# MCU023_MSP432E_Ethernet_Power.net
KiCad netlist of a schematic drawn in Altium Designer
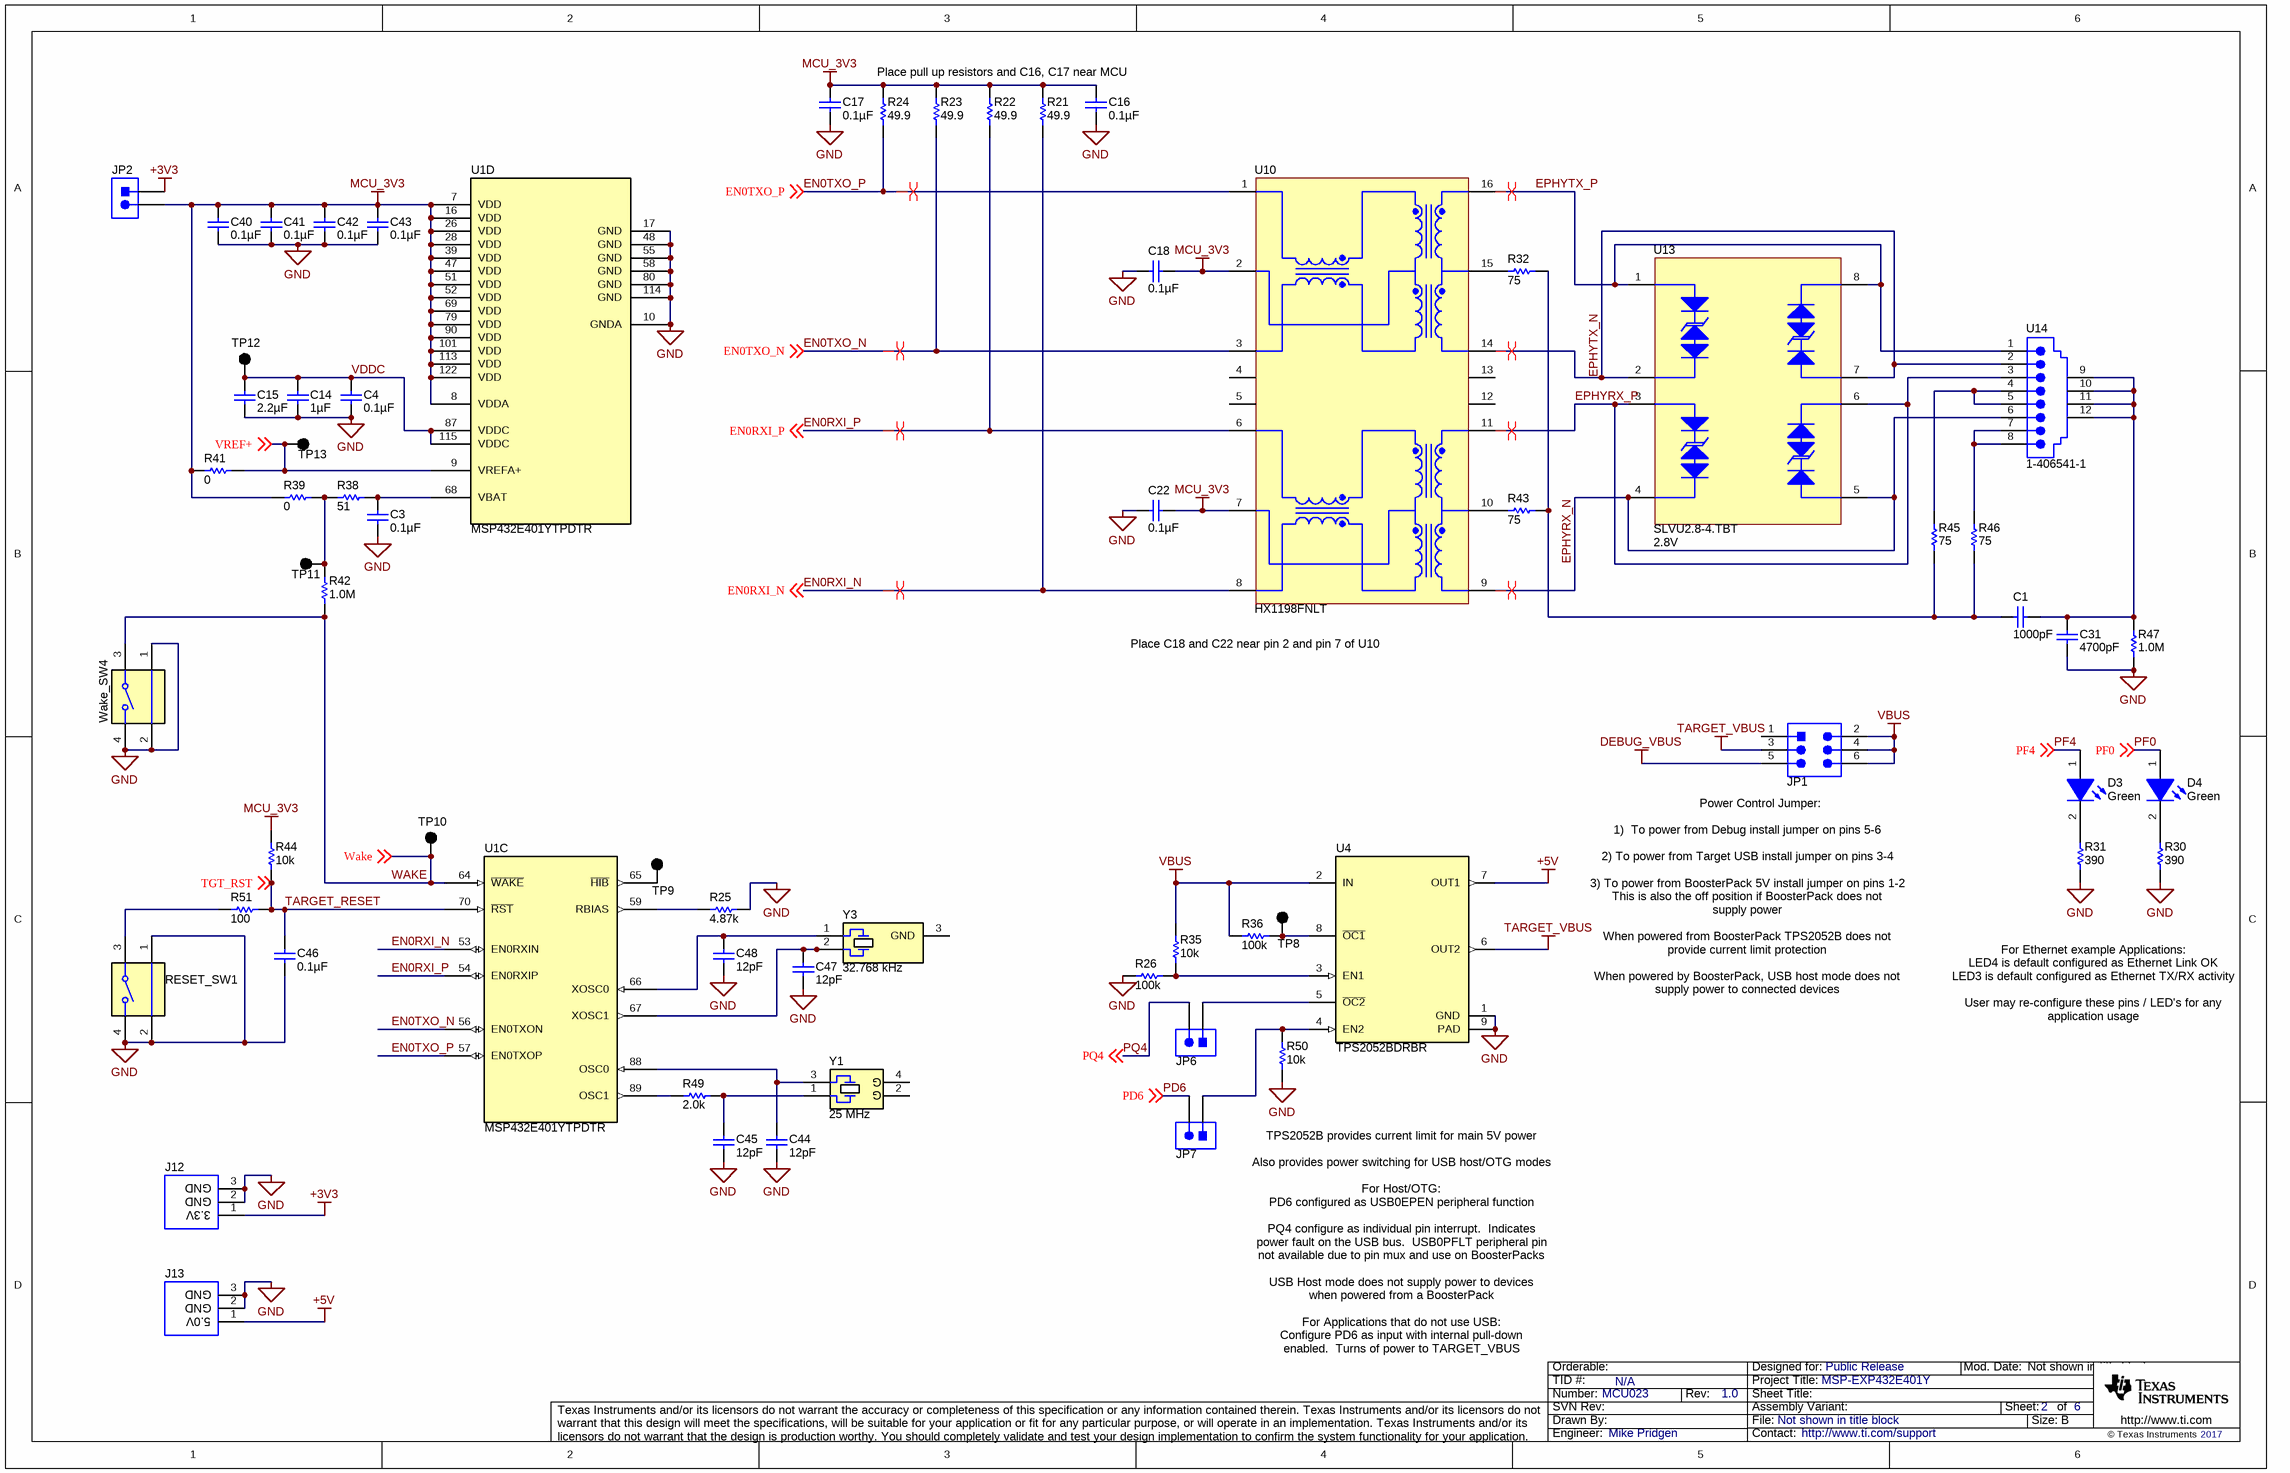
[diagram p0: MCU023_MSP432E_Ethernet_Power.SchDoc]

(export (version "E")
  (design (tool "Eeschema 10.0.6"))
  (components
    (comp (ref "C1")
      (value "C1210C102KGRACTU")
      (footprint "1210_270")
      (description "CAP, CERM, 1000 pF, 2000 V, +/- 10%, X7R, 1210")
      (fields
        (field (name "VALUEDISPLAYED") "1000pF")
        (field (name "MANUFACTURER") "Kemet")
        (field (name "PUBLISHER") "Texas Instruments")
      )
      (libsource (lib "Capacitor_Ceramic") (part "C1210C102KGRACTU"))
    )
    (comp (ref "C3")
      (value "GRM155R71C104KA88D")
      (footprint "0402")
      (description "CAP, CERM, 0.1 µF, 16 V, +/- 10%, X7R, 0402")
      (fields
        (field (name "VALUEDISPLAYED") "0.1µF")
        (field (name "MANUFACTURER") "MuRata")
        (field (name "PUBLISHER") "Texas Instruments")
      )
      (libsource (lib "Capacitor_Ceramic") (part "GRM155R71C104KA88D"))
    )
    (comp (ref "C4")
      (value "GRM155R71C104KA88D")
      (footprint "0402")
      (description "CAP, CERM, 0.1 µF, 16 V, +/- 10%, X7R, 0402")
      (fields
        (field (name "VALUEDISPLAYED") "0.1µF")
        (field (name "MANUFACTURER") "MuRata")
        (field (name "PUBLISHER") "Texas Instruments")
      )
      (libsource (lib "Capacitor_Ceramic") (part "GRM155R71C104KA88D"))
    )
    (comp (ref "C14")
      (value "GRM155R61A105KE15D")
      (footprint "0402")
      (description "CAP, CERM, 1 µF, 10 V, +/- 10%, X5R, 0402")
      (fields
        (field (name "VALUEDISPLAYED") "1µF")
        (field (name "MANUFACTURER") "MuRata")
        (field (name "PUBLISHER") "Texas Instruments")
      )
      (libsource (lib "Capacitor_Ceramic") (part "GRM155R61A105KE15D"))
    )
    (comp (ref "C15")
      (value "GRM188R61C225KE15D")
      (footprint "0603")
      (description "CAP, CERM, 2.2 µF, 16 V, +/- 10%, X5R, 0603")
      (fields
        (field (name "VALUEDISPLAYED") "2.2µF")
        (field (name "MANUFACTURER") "MuRata")
        (field (name "PUBLISHER") "Texas Instruments")
      )
      (libsource (lib "Capacitor_Ceramic") (part "GRM188R61C225KE15D"))
    )
    (comp (ref "C16")
      (value "GRM155R71C104KA88D")
      (footprint "0402")
      (description "CAP, CERM, 0.1 µF, 16 V, +/- 10%, X7R, 0402")
      (fields
        (field (name "VALUEDISPLAYED") "0.1µF")
        (field (name "MANUFACTURER") "MuRata")
        (field (name "PUBLISHER") "Texas Instruments")
      )
      (libsource (lib "Capacitor_Ceramic") (part "GRM155R71C104KA88D"))
    )
    (comp (ref "C17")
      (value "GRM155R71C104KA88D")
      (footprint "0402")
      (description "CAP, CERM, 0.1 µF, 16 V, +/- 10%, X7R, 0402")
      (fields
        (field (name "VALUEDISPLAYED") "0.1µF")
        (field (name "MANUFACTURER") "MuRata")
        (field (name "PUBLISHER") "Texas Instruments")
      )
      (libsource (lib "Capacitor_Ceramic") (part "GRM155R71C104KA88D"))
    )
    (comp (ref "C18")
      (value "GRM155R71C104KA88D")
      (footprint "0402")
      (description "CAP, CERM, 0.1 µF, 16 V, +/- 10%, X7R, 0402")
      (fields
        (field (name "VALUEDISPLAYED") "0.1µF")
        (field (name "MANUFACTURER") "MuRata")
        (field (name "PUBLISHER") "Texas Instruments")
      )
      (libsource (lib "Capacitor_Ceramic") (part "GRM155R71C104KA88D"))
    )
    (comp (ref "C22")
      (value "GRM155R71C104KA88D")
      (footprint "0402")
      (description "CAP, CERM, 0.1 µF, 16 V, +/- 10%, X7R, 0402")
      (fields
        (field (name "VALUEDISPLAYED") "0.1µF")
        (field (name "MANUFACTURER") "MuRata")
        (field (name "PUBLISHER") "Texas Instruments")
      )
      (libsource (lib "Capacitor_Ceramic") (part "GRM155R71C104KA88D"))
    )
    (comp (ref "C31")
      (value "1812GC472KAT1A")
      (footprint "1812_254")
      (description "CAP, CERM, 4700 pF, 2000 V, +/- 10%, X7R, 1812")
      (fields
        (field (name "VALUEDISPLAYED") "4700pF")
        (field (name "MANUFACTURER") "AVX")
        (field (name "PUBLISHER") "Texas Instruments")
      )
      (libsource (lib "Capacitor_Ceramic") (part "1812GC472KAT1A"))
    )
    (comp (ref "C40")
      (value "GRM155R71C104KA88D")
      (footprint "0402")
      (description "CAP, CERM, 0.1 µF, 16 V, +/- 10%, X7R, 0402")
      (fields
        (field (name "VALUEDISPLAYED") "0.1µF")
        (field (name "MANUFACTURER") "MuRata")
        (field (name "PUBLISHER") "Texas Instruments")
      )
      (libsource (lib "Capacitor_Ceramic") (part "GRM155R71C104KA88D"))
    )
    (comp (ref "C41")
      (value "GRM155R71C104KA88D")
      (footprint "0402")
      (description "CAP, CERM, 0.1 µF, 16 V, +/- 10%, X7R, 0402")
      (fields
        (field (name "VALUEDISPLAYED") "0.1µF")
        (field (name "MANUFACTURER") "MuRata")
        (field (name "PUBLISHER") "Texas Instruments")
      )
      (libsource (lib "Capacitor_Ceramic") (part "GRM155R71C104KA88D"))
    )
    (comp (ref "C42")
      (value "GRM155R71C104KA88D")
      (footprint "0402")
      (description "CAP, CERM, 0.1 µF, 16 V, +/- 10%, X7R, 0402")
      (fields
        (field (name "VALUEDISPLAYED") "0.1µF")
        (field (name "MANUFACTURER") "MuRata")
        (field (name "PUBLISHER") "Texas Instruments")
      )
      (libsource (lib "Capacitor_Ceramic") (part "GRM155R71C104KA88D"))
    )
    (comp (ref "C43")
      (value "GRM155R71C104KA88D")
      (footprint "0402")
      (description "CAP, CERM, 0.1 µF, 16 V, +/- 10%, X7R, 0402")
      (fields
        (field (name "VALUEDISPLAYED") "0.1µF")
        (field (name "MANUFACTURER") "MuRata")
        (field (name "PUBLISHER") "Texas Instruments")
      )
      (libsource (lib "Capacitor_Ceramic") (part "GRM155R71C104KA88D"))
    )
    (comp (ref "C44")
      (value "GRM1555C1H120JA01D")
      (footprint "0402")
      (description "CAP, CERM, 12 pF, 50 V, +/- 5%, C0G/NP0, 0402")
      (fields
        (field (name "VALUEDISPLAYED") "12pF")
        (field (name "MANUFACTURER") "MuRata")
        (field (name "PUBLISHER") "Texas Instruments")
      )
      (libsource (lib "Capacitor_Ceramic") (part "GRM1555C1H120JA01D"))
    )
    (comp (ref "C45")
      (value "GRM1555C1H120JA01D")
      (footprint "0402")
      (description "CAP, CERM, 12 pF, 50 V, +/- 5%, C0G/NP0, 0402")
      (fields
        (field (name "VALUEDISPLAYED") "12pF")
        (field (name "MANUFACTURER") "MuRata")
        (field (name "PUBLISHER") "Texas Instruments")
      )
      (libsource (lib "Capacitor_Ceramic") (part "GRM1555C1H120JA01D"))
    )
    (comp (ref "C46")
      (value "GRM155R71C104KA88D")
      (footprint "0402")
      (description "CAP, CERM, 0.1 µF, 16 V, +/- 10%, X7R, 0402")
      (fields
        (field (name "VALUEDISPLAYED") "0.1µF")
        (field (name "MANUFACTURER") "MuRata")
        (field (name "PUBLISHER") "Texas Instruments")
      )
      (libsource (lib "Capacitor_Ceramic") (part "GRM155R71C104KA88D"))
    )
    (comp (ref "C47")
      (value "GRM1555C1H120JA01D")
      (footprint "0402")
      (description "CAP, CERM, 12 pF, 50 V, +/- 5%, C0G/NP0, 0402")
      (fields
        (field (name "VALUEDISPLAYED") "12pF")
        (field (name "MANUFACTURER") "MuRata")
        (field (name "PUBLISHER") "Texas Instruments")
      )
      (libsource (lib "Capacitor_Ceramic") (part "GRM1555C1H120JA01D"))
    )
    (comp (ref "C48")
      (value "GRM1555C1H120JA01D")
      (footprint "0402")
      (description "CAP, CERM, 12 pF, 50 V, +/- 5%, C0G/NP0, 0402")
      (fields
        (field (name "VALUEDISPLAYED") "12pF")
        (field (name "MANUFACTURER") "MuRata")
        (field (name "PUBLISHER") "Texas Instruments")
      )
      (libsource (lib "Capacitor_Ceramic") (part "GRM1555C1H120JA01D"))
    )
    (comp (ref "D3")
      (value "Green")
      (footprint "LED_LTST-C190")
      (description "LED, Green, SMD")
      (fields
        (field (name "PARTNUMBER") "LTST-C190GKT")
        (field (name "MANUFACTURER") "Lite-On")
        (field (name "PUBLISHER") "Texas Instruments")
      )
      (libsource (lib "LED") (part "LTST-C190GKT"))
    )
    (comp (ref "D4")
      (value "Green")
      (footprint "LED_LTST-C190")
      (description "LED, Green, SMD")
      (fields
        (field (name "PARTNUMBER") "LTST-C190GKT")
        (field (name "MANUFACTURER") "Lite-On")
        (field (name "PUBLISHER") "Texas Instruments")
      )
      (libsource (lib "LED") (part "LTST-C190GKT"))
    )
    (comp (ref "J12")
      (value "PEC03SAAN")
      (footprint "PEC03SAAN_Launchpad_3V3")
      (description "Header, 100mil, 3x1, Tin, TH")
      (fields
        (field (name "MANUFACTURER") "Sullins Connector Solutions")
        (field (name "SYMBOLCREATOR") "a0412235")
        (field (name "PUBLISHER") "Texas Instruments")
      )
      (libsource (lib "") (part "PEC03SAAN_1"))
    )
    (comp (ref "J13")
      (value "PEC03SAAN")
      (footprint "PEC03SAAN_Launchpad_5V0")
      (description "Header, 100mil, 3x1, Tin, TH")
      (fields
        (field (name "MANUFACTURER") "Sullins Connector Solutions")
        (field (name "SYMBOLCREATOR") "a0412235")
        (field (name "PUBLISHER") "Texas Instruments")
      )
      (libsource (lib "Connectors_Sullins") (part "PEC03SAAN"))
    )
    (comp (ref "JP1")
      (value "PEC03DAAN")
      (footprint "SULLINS_PEC03DAAN")
      (description "Header, 100mil, 3x2, Tin, TH")
      (fields
        (field (name "MANUFACTURER") "Sullins Connector Solutions")
        (field (name "SYMBOLCREATOR") "a0412235")
        (field (name "PUBLISHER") "Texas Instruments")
      )
      (libsource (lib "Connectors_Sullins") (part "PEC03DAAN"))
    )
    (comp (ref "JP2")
      (value "PEC02SAAN")
      (footprint "CONN_PEC02SAAN")
      (description "Header, 100mil, 2x1, Tin, TH")
      (fields
        (field (name "MANUFACTURER") "Sullins Connector Solutions")
        (field (name "SYMBOLCREATOR") "a0412235")
        (field (name "PUBLISHER") "Texas Instruments")
      )
      (libsource (lib "Connectors_Sullins") (part "PEC02SAAN"))
    )
    (comp (ref "JP6")
      (value "PEC02SAAN")
      (footprint "CONN_PEC02SAAN")
      (description "Header, 100mil, 2x1, Tin, TH")
      (fields
        (field (name "MANUFACTURER") "Sullins Connector Solutions")
        (field (name "SYMBOLCREATOR") "a0412235")
        (field (name "PUBLISHER") "Texas Instruments")
      )
      (libsource (lib "Connectors_Sullins") (part "PEC02SAAN"))
    )
    (comp (ref "JP7")
      (value "PEC02SAAN")
      (footprint "CONN_PEC02SAAN")
      (description "Header, 100mil, 2x1, Tin, TH")
      (fields
        (field (name "MANUFACTURER") "Sullins Connector Solutions")
        (field (name "SYMBOLCREATOR") "a0412235")
        (field (name "PUBLISHER") "Texas Instruments")
      )
      (libsource (lib "Connectors_Sullins") (part "PEC02SAAN"))
    )
    (comp (ref "R21")
      (value "CRCW040249R9FKED")
      (footprint "0402")
      (description "RES, 49.9, 1%, 0.063 W, 0402")
      (fields
        (field (name "VALUEDISPLAYED") "49.9")
        (field (name "MANUFACTURER") "Vishay-Dale")
        (field (name "PUBLISHER") "Texas Instruments")
      )
      (libsource (lib "Resistor_0402") (part "CRCW040249R9FKED"))
    )
    (comp (ref "R22")
      (value "CRCW040249R9FKED")
      (footprint "0402")
      (description "RES, 49.9, 1%, 0.063 W, 0402")
      (fields
        (field (name "VALUEDISPLAYED") "49.9")
        (field (name "MANUFACTURER") "Vishay-Dale")
        (field (name "PUBLISHER") "Texas Instruments")
      )
      (libsource (lib "Resistor_0402") (part "CRCW040249R9FKED"))
    )
    (comp (ref "R23")
      (value "CRCW040249R9FKED")
      (footprint "0402")
      (description "RES, 49.9, 1%, 0.063 W, 0402")
      (fields
        (field (name "VALUEDISPLAYED") "49.9")
        (field (name "MANUFACTURER") "Vishay-Dale")
        (field (name "PUBLISHER") "Texas Instruments")
      )
      (libsource (lib "Resistor_0402") (part "CRCW040249R9FKED"))
    )
    (comp (ref "R24")
      (value "CRCW040249R9FKED")
      (footprint "0402")
      (description "RES, 49.9, 1%, 0.063 W, 0402")
      (fields
        (field (name "VALUEDISPLAYED") "49.9")
        (field (name "MANUFACTURER") "Vishay-Dale")
        (field (name "PUBLISHER") "Texas Instruments")
      )
      (libsource (lib "Resistor_0402") (part "CRCW040249R9FKED"))
    )
    (comp (ref "R25")
      (value "CRCW04024K87FKED")
      (footprint "0402")
      (description "RES, 4.87 k, 1%, 0.063 W, 0402")
      (fields
        (field (name "VALUEDISPLAYED") "4.87k")
        (field (name "MANUFACTURER") "Vishay-Dale")
        (field (name "PUBLISHER") "Texas Instruments")
      )
      (libsource (lib "Resistor_0402") (part "CRCW04024K87FKED"))
    )
    (comp (ref "R26")
      (value "CRCW0402100KJNED")
      (footprint "0402")
      (description "RES, 100 k, 5%, 0.063 W, 0402")
      (fields
        (field (name "VALUEDISPLAYED") "100k")
        (field (name "MANUFACTURER") "Vishay-Dale")
        (field (name "PUBLISHER") "Texas Instruments")
      )
      (libsource (lib "Resistor_0402") (part "CRCW0402100KJNED"))
    )
    (comp (ref "R30")
      (value "CRCW0402390RJNED")
      (footprint "0402")
      (description "RES, 390, 5%, 0.063 W, 0402")
      (fields
        (field (name "VALUEDISPLAYED") "390")
        (field (name "MANUFACTURER") "Vishay-Dale")
        (field (name "PUBLISHER") "Texas Instruments")
      )
      (libsource (lib "Resistor_0402") (part "CRCW0402390RJNED"))
    )
    (comp (ref "R31")
      (value "CRCW0402390RJNED")
      (footprint "0402")
      (description "RES, 390, 5%, 0.063 W, 0402")
      (fields
        (field (name "VALUEDISPLAYED") "390")
        (field (name "MANUFACTURER") "Vishay-Dale")
        (field (name "PUBLISHER") "Texas Instruments")
      )
      (libsource (lib "Resistor_0402") (part "CRCW0402390RJNED"))
    )
    (comp (ref "R32")
      (value "CRCW040275R0JNED")
      (footprint "0402")
      (description "RES, 75, 5%, 0.063 W, 0402")
      (fields
        (field (name "VALUEDISPLAYED") "75")
        (field (name "MANUFACTURER") "Vishay-Dale")
        (field (name "PUBLISHER") "Texas Instruments")
      )
      (libsource (lib "Resistor_0402") (part "CRCW040275R0JNED"))
    )
    (comp (ref "R35")
      (value "CRCW040210K0JNED")
      (footprint "0402")
      (description "RES, 10 k, 5%, 0.063 W, 0402")
      (fields
        (field (name "VALUEDISPLAYED") "10k")
        (field (name "MANUFACTURER") "Vishay-Dale")
        (field (name "PUBLISHER") "Texas Instruments")
      )
      (libsource (lib "Resistor_0402") (part "CRCW040210K0JNED"))
    )
    (comp (ref "R36")
      (value "CRCW0402100KJNED")
      (footprint "0402")
      (description "RES, 100 k, 5%, 0.063 W, 0402")
      (fields
        (field (name "VALUEDISPLAYED") "100k")
        (field (name "MANUFACTURER") "Vishay-Dale")
        (field (name "PUBLISHER") "Texas Instruments")
      )
      (libsource (lib "Resistor_0402") (part "CRCW0402100KJNED"))
    )
    (comp (ref "R38")
      (value "CRCW040251R0JNED")
      (footprint "0402")
      (description "RES, 51, 5%, 0.063 W, 0402")
      (fields
        (field (name "VALUEDISPLAYED") "51")
        (field (name "MANUFACTURER") "Vishay-Dale")
        (field (name "PUBLISHER") "Texas Instruments")
      )
      (libsource (lib "Resistor_0402") (part "CRCW040251R0JNED"))
    )
    (comp (ref "R39")
      (value "ERJ-2GE0R00X")
      (footprint "0402")
      (description "RES, 0, 5%, 0.063 W, 0402")
      (fields
        (field (name "VALUEDISPLAYED") "0")
        (field (name "MANUFACTURER") "Panasonic")
        (field (name "PUBLISHER") "Texas Instruments")
      )
      (libsource (lib "Resistor_0402") (part "ERJ-2GE0R00X"))
    )
    (comp (ref "R41")
      (value "ERJ-2GE0R00X")
      (footprint "0402")
      (description "RES, 0, 5%, 0.063 W, 0402")
      (fields
        (field (name "VALUEDISPLAYED") "0")
        (field (name "MANUFACTURER") "Panasonic")
        (field (name "PUBLISHER") "Texas Instruments")
      )
      (libsource (lib "Resistor_0402") (part "ERJ-2GE0R00X"))
    )
    (comp (ref "R42")
      (value "CRCW04021M00JNED")
      (footprint "0402")
      (description "RES, 1.0 M, 5%, 0.063 W, 0402")
      (fields
        (field (name "VALUEDISPLAYED") "1.0M")
        (field (name "MANUFACTURER") "Vishay-Dale")
        (field (name "PUBLISHER") "Texas Instruments")
      )
      (libsource (lib "Resistor_0402") (part "CRCW04021M00JNED"))
    )
    (comp (ref "R43")
      (value "CRCW040275R0JNED")
      (footprint "0402")
      (description "RES, 75, 5%, 0.063 W, 0402")
      (fields
        (field (name "VALUEDISPLAYED") "75")
        (field (name "MANUFACTURER") "Vishay-Dale")
        (field (name "PUBLISHER") "Texas Instruments")
      )
      (libsource (lib "Resistor_0402") (part "CRCW040275R0JNED"))
    )
    (comp (ref "R44")
      (value "CRCW040210K0JNED")
      (footprint "0402")
      (description "RES, 10 k, 5%, 0.063 W, 0402")
      (fields
        (field (name "VALUEDISPLAYED") "10k")
        (field (name "MANUFACTURER") "Vishay-Dale")
        (field (name "PUBLISHER") "Texas Instruments")
      )
      (libsource (lib "Resistor_0402") (part "CRCW040210K0JNED"))
    )
    (comp (ref "R45")
      (value "CRCW040275R0JNED")
      (footprint "0402")
      (description "RES, 75, 5%, 0.063 W, 0402")
      (fields
        (field (name "VALUEDISPLAYED") "75")
        (field (name "MANUFACTURER") "Vishay-Dale")
        (field (name "PUBLISHER") "Texas Instruments")
      )
      (libsource (lib "Resistor_0402") (part "CRCW040275R0JNED"))
    )
    (comp (ref "R46")
      (value "CRCW040275R0JNED")
      (footprint "0402")
      (description "RES, 75, 5%, 0.063 W, 0402")
      (fields
        (field (name "VALUEDISPLAYED") "75")
        (field (name "MANUFACTURER") "Vishay-Dale")
        (field (name "PUBLISHER") "Texas Instruments")
      )
      (libsource (lib "Resistor_0402") (part "CRCW040275R0JNED"))
    )
    (comp (ref "R47")
      (value "CRCW12061M00JNEA")
      (footprint "1206")
      (description "RES, 1.0 M, 5%, 0.25 W, 1206")
      (fields
        (field (name "VALUEDISPLAYED") "1.0M")
        (field (name "MANUFACTURER") "Vishay-Dale")
        (field (name "PUBLISHER") "Texas Instruments")
      )
      (libsource (lib "Resistor_1206") (part "CRCW12061M00JNEA"))
    )
    (comp (ref "R49")
      (value "CRCW04022K00JNED")
      (footprint "0402")
      (description "RES, 2.0 k, 5%, 0.063 W, 0402")
      (fields
        (field (name "VALUEDISPLAYED") "2.0k")
        (field (name "MANUFACTURER") "Vishay-Dale")
        (field (name "PUBLISHER") "Texas Instruments")
      )
      (libsource (lib "Resistor_0402") (part "CRCW04022K00JNED"))
    )
    (comp (ref "R50")
      (value "CRCW040210K0JNED")
      (footprint "0402")
      (description "RES, 10 k, 5%, 0.063 W, 0402")
      (fields
        (field (name "VALUEDISPLAYED") "10k")
        (field (name "MANUFACTURER") "Vishay-Dale")
        (field (name "PUBLISHER") "Texas Instruments")
      )
      (libsource (lib "Resistor_0402") (part "CRCW040210K0JNED"))
    )
    (comp (ref "R51")
      (value "CRCW0402100RJNED")
      (footprint "0402")
      (description "RES, 100, 5%, 0.063 W, 0402")
      (fields
        (field (name "VALUEDISPLAYED") "100")
        (field (name "MANUFACTURER") "Vishay-Dale")
        (field (name "PUBLISHER") "Texas Instruments")
      )
      (libsource (lib "Resistor_0402") (part "CRCW0402100RJNED"))
    )
    (comp (ref "RESET_SW1")
      (value "1188E-1K2-V-TR")
      (footprint "SW_1188E")
      (description "Switch, SPST, 0.05 A, 12 VDC, SMD")
      (fields
        (field (name "MANUFACTURER") "Diptronics")
        (field (name "SYMBOLCREATOR") "Altium")
        (field (name "PUBLISHER") "Texas Instruments")
      )
      (libsource (lib "Switches") (part "1188E-1K2-V-TR"))
    )
    (comp (ref "TP8")
      (value "5001")
      (footprint "Keystone5001")
      (description "Test Point, Miniature, Black, TH")
      (fields (field (name "MANUFACTURER") "Keystone") (field (name "PUBLISHER") "Texas Instruments"))
      (libsource (lib "Connectors_Keystone") (part "5001"))
    )
    (comp (ref "TP9")
      (value "5001")
      (footprint "Keystone5001")
      (description "Test Point, Miniature, Black, TH")
      (fields (field (name "MANUFACTURER") "Keystone") (field (name "PUBLISHER") "Texas Instruments"))
      (libsource (lib "Connectors_Keystone") (part "5001"))
    )
    (comp (ref "TP10")
      (value "5001")
      (footprint "Keystone5001")
      (description "Test Point, Miniature, Black, TH")
      (fields (field (name "MANUFACTURER") "Keystone") (field (name "PUBLISHER") "Texas Instruments"))
      (libsource (lib "Connectors_Keystone") (part "5001"))
    )
    (comp (ref "TP11")
      (value "5001")
      (footprint "Keystone5001")
      (description "Test Point, Miniature, Black, TH")
      (fields (field (name "MANUFACTURER") "Keystone") (field (name "PUBLISHER") "Texas Instruments"))
      (libsource (lib "Connectors_Keystone") (part "5001"))
    )
    (comp (ref "TP12")
      (value "5001")
      (footprint "Keystone5001")
      (description "Test Point, Miniature, Black, TH")
      (fields (field (name "MANUFACTURER") "Keystone") (field (name "PUBLISHER") "Texas Instruments"))
      (libsource (lib "Connectors_Keystone") (part "5001"))
    )
    (comp (ref "TP13")
      (value "5001")
      (footprint "Keystone5001")
      (description "Test Point, Miniature, Black, TH")
      (fields (field (name "MANUFACTURER") "Keystone") (field (name "PUBLISHER") "Texas Instruments"))
      (libsource (lib "Connectors_Keystone") (part "5001"))
    )
    (comp (ref "U1")
      (value "MSP432E401YTPDTR")
      (footprint "PDT0128A")
      (description "IoT enabled High performance 32-bit ARM(R) Cortex(R)-M4F based MCU, PDT0128A (TQFP-128)")
      (fields
        (field (name "MANUFACTURER") "Texas Instruments")
        (field (name "SYMBOLCREATOR") "a0411947")
        (field (name "PUBLISHER") "Texas Instruments")
      )
      (libsource (lib "TI_Pre_Release") (part "TM4C1294NCPDTI3R"))
    )
    (comp (ref "U4")
      (value "TPS2052BDRBR")
      (footprint "DRB0008B")
      (description "Current-Limited, Power-Distribution Switches, DRB0008B (VSON-8)")
      (fields
        (field (name "ALTERNATE PARTNUMBER") "TPS2052BDRBT")
        (field (name "MANUFACTURER") "Texas Instruments")
        (field (name "SYMBOLCREATOR") "a0411947")
        (field (name "PUBLISHER") "Texas Instruments")
      )
      (libsource (lib "TI_Pre_Release1") (part "TPS2052BDRBR"))
    )
    (comp (ref "U10")
      (value "HX1198FNLT")
      (footprint "Pulse_HX1198FNLT")
      (description "Transformer, 350 uH, SMT")
      (fields
        (field (name "MANUFACTURER") "Pulse Engineering")
        (field (name "PUBLISHER") "Texas Instruments")
      )
      (libsource (lib "Altium Vault - TI") (part "Pulse_HX1198FNLT"))
    )
    (comp (ref "U13")
      (value "SLVU2.8-4.TBT")
      (footprint "SOIC-8")
      (description "Diode, TVS, Uni, 2.8 V, 15 Vc, SOIC-8")
      (fields
        (field (name "ALTIUM_VALUE") "2.8V")
        (field (name "MANUFACTURER") "Semtech")
        (field (name "SYMBOLCREATOR") "Altium")
        (field (name "PUBLISHER") "Texas Instruments")
      )
      (libsource (lib "ZenerDiodes") (part "SLVU2.8-4.TBT"))
    )
    (comp (ref "U14")
      (value "1-406541-1")
      (footprint "TEC_1-406541-1")
      (description "RJ-45, No LED, tab up, R/A, TH")
      (fields
        (field (name "MANUFACTURER") "TE Connectivity")
        (field (name "SYMBOLCREATOR") "x0208326")
        (field (name "PUBLISHER") "Texas Instruments")
      )
      (libsource (lib "Connectors_TE_Connectivity") (part "1-406541-1"))
    )
    (comp (ref "Wake_SW4")
      (value "1188E-1K2-V-TR")
      (footprint "SW_1188E")
      (description "Switch, SPST, 0.05 A, 12 VDC, SMD")
      (fields
        (field (name "MANUFACTURER") "Diptronics")
        (field (name "SYMBOLCREATOR") "Altium")
        (field (name "PUBLISHER") "Texas Instruments")
      )
      (libsource (lib "Switches") (part "1188E-1K2-V-TR"))
    )
    (comp (ref "Y1")
      (value "NX3225GA-25.000M-STD-CRG-2")
      (footprint "NDK_NX3225GA")
      (description "Crystal, 25 MHz, 8pF, SMD")
      (fields
        (field (name "MANUFACTURER") "NDK")
        (field (name "FREQUENCY_FIXED") "25 MHz")
        (field (name "SYMBOLCREATOR") "a0412235")
        (field (name "PUBLISHER") "Texas Instruments")
      )
      (libsource (lib "Oscillators") (part "NX3225GA-25.000M-STD-CRG-2"))
    )
    (comp (ref "Y3")
      (value "CMR200T-32.768KDZY-UT")
      (footprint "CFM_CMR200T")
      (description "Crystal, 32.768 MHz,  SMD")
      (fields
        (field (name "MANUFACTURER") "Citizen Finetech Miyota ")
        (field (name "FREQUENCY_FIXED") "32.768 kHz")
        (field (name "SYMBOLCREATOR") "Altium")
        (field (name "PUBLISHER") "Texas Instruments")
      )
      (libsource (lib "Oscillators") (part "CMR200T-32.768KDZY-UT"))
    )
  )
  (nets
    (net (code "1") (name "+3V3") (class "Default")
      (node (ref "J12") (pin "1") (pinfunction "1_1") (pintype "passive"))
      (node (ref "JP2") (pin "1") (pinfunction "1_1") (pintype "passive"))
    )
    (net (code "2") (name "+5V") (class "Default")
      (node (ref "J13") (pin "1") (pinfunction "1_1") (pintype "passive"))
      (node (ref "U4") (pin "7") (pinfunction "OUT1_7") (pintype "output"))
    )
    (net (code "3") (name "/EPHYRX_N") (class "Default")
      (node (ref "U10") (pin "9") (pinfunction "RX-_9") (pintype "passive"))
      (node (ref "U13") (pin "4") (pinfunction "4_4") (pintype "passive"))
      (node (ref "U13") (pin "5") (pinfunction "5_5") (pintype "passive"))
      (node (ref "U14") (pin "6") (pinfunction "6_6") (pintype "passive"))
    )
    (net (code "4") (name "/EPHYRX_P") (class "Default")
      (node (ref "U10") (pin "11") (pinfunction "RX+_11") (pintype "passive"))
      (node (ref "U13") (pin "3") (pinfunction "3_3") (pintype "passive"))
      (node (ref "U13") (pin "6") (pinfunction "6_6") (pintype "passive"))
      (node (ref "U14") (pin "3") (pinfunction "3_3") (pintype "passive"))
    )
    (net (code "5") (name "/EPHYTX_N") (class "Default")
      (node (ref "U10") (pin "14") (pinfunction "TX-_14") (pintype "passive"))
      (node (ref "U13") (pin "2") (pinfunction "2_2") (pintype "passive"))
      (node (ref "U13") (pin "7") (pinfunction "7_7") (pintype "passive"))
      (node (ref "U14") (pin "2") (pinfunction "2_2") (pintype "passive"))
    )
    (net (code "6") (name "/EPHYTX_P") (class "Default")
      (node (ref "U10") (pin "16") (pinfunction "TX+_16") (pintype "passive"))
      (node (ref "U13") (pin "1") (pinfunction "1_1") (pintype "passive"))
      (node (ref "U13") (pin "8") (pinfunction "8_8") (pintype "passive"))
      (node (ref "U14") (pin "1") (pinfunction "1_1") (pintype "passive"))
    )
    (net (code "7") (name "/VDDC") (class "Default")
      (node (ref "C14") (pin "1") (pinfunction "1_1") (pintype "passive"))
      (node (ref "C15") (pin "1") (pinfunction "1_1") (pintype "passive"))
      (node (ref "C4") (pin "2") (pinfunction "2_2") (pintype "passive"))
      (node (ref "TP12") (pin "1") (pintype "passive"))
      (node (ref "U1") (pin "115") (pinfunction "VDDC_115") (pintype "power_in"))
      (node (ref "U1") (pin "87") (pinfunction "VDDC_87") (pintype "power_in"))
    )
    (net (code "8") (name "DEBUG_VBUS") (class "Default")
      (node (ref "JP1") (pin "5") (pinfunction "5_5") (pintype "passive"))
    )
    (net (code "9") (name "EN0RXI_N") (class "Default")
      (node (ref "R21") (pin "1") (pinfunction "1_1") (pintype "passive"))
      (node (ref "U1") (pin "53") (pinfunction "EN0RXIN_53") (pintype "bidirectional"))
      (node (ref "U10") (pin "8") (pinfunction "RD-_8") (pintype "passive"))
    )
    (net (code "10") (name "EN0RXI_P") (class "Default")
      (node (ref "R22") (pin "1") (pinfunction "1_1") (pintype "passive"))
      (node (ref "U1") (pin "54") (pinfunction "EN0RXIP_54") (pintype "bidirectional"))
      (node (ref "U10") (pin "6") (pinfunction "RD+_6") (pintype "passive"))
    )
    (net (code "11") (name "EN0TXO_N") (class "Default")
      (node (ref "R23") (pin "1") (pinfunction "1_1") (pintype "passive"))
      (node (ref "U1") (pin "56") (pinfunction "EN0TXON_56") (pintype "bidirectional"))
      (node (ref "U10") (pin "3") (pinfunction "TD-_3") (pintype "passive"))
    )
    (net (code "12") (name "EN0TXO_P") (class "Default")
      (node (ref "R24") (pin "1") (pinfunction "1_1") (pintype "passive"))
      (node (ref "U1") (pin "57") (pinfunction "EN0TXOP_57") (pintype "bidirectional"))
      (node (ref "U10") (pin "1") (pinfunction "TD+_1") (pintype "passive"))
    )
    (net (code "13") (name "GND") (class "Default")
      (node (ref "C14") (pin "2") (pinfunction "2_2") (pintype "passive"))
      (node (ref "C15") (pin "2") (pinfunction "2_2") (pintype "passive"))
      (node (ref "C16") (pin "1") (pinfunction "1_1") (pintype "passive"))
      (node (ref "C17") (pin "1") (pinfunction "1_1") (pintype "passive"))
      (node (ref "C18") (pin "2") (pinfunction "2_2") (pintype "passive"))
      (node (ref "C22") (pin "2") (pinfunction "2_2") (pintype "passive"))
      (node (ref "C3") (pin "1") (pinfunction "1_1") (pintype "passive"))
      (node (ref "C31") (pin "2") (pinfunction "2_2") (pintype "passive"))
      (node (ref "C4") (pin "1") (pinfunction "1_1") (pintype "passive"))
      (node (ref "C40") (pin "1") (pinfunction "1_1") (pintype "passive"))
      (node (ref "C41") (pin "1") (pinfunction "1_1") (pintype "passive"))
      (node (ref "C42") (pin "1") (pinfunction "1_1") (pintype "passive"))
      (node (ref "C43") (pin "1") (pinfunction "1_1") (pintype "passive"))
      (node (ref "C44") (pin "2") (pinfunction "2_2") (pintype "passive"))
      (node (ref "C45") (pin "2") (pinfunction "2_2") (pintype "passive"))
      (node (ref "C46") (pin "1") (pinfunction "1_1") (pintype "passive"))
      (node (ref "C47") (pin "2") (pinfunction "2_2") (pintype "passive"))
      (node (ref "C48") (pin "2") (pinfunction "2_2") (pintype "passive"))
      (node (ref "J12") (pin "2") (pinfunction "2_2") (pintype "passive"))
      (node (ref "J12") (pin "3") (pinfunction "3_3") (pintype "passive"))
      (node (ref "J13") (pin "2") (pinfunction "2_2") (pintype "passive"))
      (node (ref "J13") (pin "3") (pinfunction "3_3") (pintype "passive"))
      (node (ref "R25") (pin "2") (pinfunction "2_2") (pintype "passive"))
      (node (ref "R26") (pin "1") (pinfunction "1_1") (pintype "passive"))
      (node (ref "R30") (pin "1") (pinfunction "1_1") (pintype "passive"))
      (node (ref "R31") (pin "1") (pinfunction "1_1") (pintype "passive"))
      (node (ref "R47") (pin "1") (pinfunction "1_1") (pintype "passive"))
      (node (ref "R50") (pin "1") (pinfunction "1_1") (pintype "passive"))
      (node (ref "RESET_SW1") (pin "1") (pinfunction "1_1") (pintype "passive"))
      (node (ref "RESET_SW1") (pin "2") (pinfunction "2_2") (pintype "passive"))
      (node (ref "RESET_SW1") (pin "4") (pinfunction "4_4") (pintype "passive"))
      (node (ref "U1") (pin "10") (pinfunction "GNDA_10") (pintype "power_in"))
      (node (ref "U1") (pin "114") (pinfunction "GND_114") (pintype "power_in"))
      (node (ref "U1") (pin "17") (pinfunction "GND_17") (pintype "power_in"))
      (node (ref "U1") (pin "48") (pinfunction "GND_48") (pintype "power_in"))
      (node (ref "U1") (pin "55") (pinfunction "GND_55") (pintype "power_in"))
      (node (ref "U1") (pin "58") (pinfunction "GND_58") (pintype "power_in"))
      (node (ref "U1") (pin "80") (pinfunction "GND_80") (pintype "power_in"))
      (node (ref "U4") (pin "1") (pinfunction "GND_1") (pintype "power_in"))
      (node (ref "U4") (pin "9") (pinfunction "PAD_9") (pintype "power_in"))
      (node (ref "Wake_SW4") (pin "1") (pinfunction "1_1") (pintype "passive"))
      (node (ref "Wake_SW4") (pin "2") (pinfunction "2_2") (pintype "passive"))
      (node (ref "Wake_SW4") (pin "4") (pinfunction "4_4") (pintype "passive"))
    )
    (net (code "14") (name "MCU_3V3") (class "Default")
      (node (ref "C16") (pin "2") (pinfunction "2_2") (pintype "passive"))
      (node (ref "C17") (pin "2") (pinfunction "2_2") (pintype "passive"))
      (node (ref "C18") (pin "1") (pinfunction "1_1") (pintype "passive"))
      (node (ref "C22") (pin "1") (pinfunction "1_1") (pintype "passive"))
      (node (ref "C40") (pin "2") (pinfunction "2_2") (pintype "passive"))
      (node (ref "C41") (pin "2") (pinfunction "2_2") (pintype "passive"))
      (node (ref "C42") (pin "2") (pinfunction "2_2") (pintype "passive"))
      (node (ref "C43") (pin "2") (pinfunction "2_2") (pintype "passive"))
      (node (ref "JP2") (pin "2") (pinfunction "2_2") (pintype "passive"))
      (node (ref "R21") (pin "2") (pinfunction "2_2") (pintype "passive"))
      (node (ref "R22") (pin "2") (pinfunction "2_2") (pintype "passive"))
      (node (ref "R23") (pin "2") (pinfunction "2_2") (pintype "passive"))
      (node (ref "R24") (pin "2") (pinfunction "2_2") (pintype "passive"))
      (node (ref "R39") (pin "1") (pinfunction "1_1") (pintype "passive"))
      (node (ref "R41") (pin "1") (pinfunction "1_1") (pintype "passive"))
      (node (ref "R44") (pin "2") (pinfunction "2_2") (pintype "passive"))
      (node (ref "U1") (pin "101") (pinfunction "VDD_101") (pintype "power_in"))
      (node (ref "U1") (pin "113") (pinfunction "VDD_113") (pintype "power_in"))
      (node (ref "U1") (pin "122") (pinfunction "VDD_122") (pintype "power_in"))
      (node (ref "U1") (pin "16") (pinfunction "VDD_16") (pintype "power_in"))
      (node (ref "U1") (pin "26") (pinfunction "VDD_26") (pintype "power_in"))
      (node (ref "U1") (pin "28") (pinfunction "VDD_28") (pintype "power_in"))
      (node (ref "U1") (pin "39") (pinfunction "VDD_39") (pintype "power_in"))
      (node (ref "U1") (pin "47") (pinfunction "VDD_47") (pintype "power_in"))
      (node (ref "U1") (pin "51") (pinfunction "VDD_51") (pintype "power_in"))
      (node (ref "U1") (pin "52") (pinfunction "VDD_52") (pintype "power_in"))
      (node (ref "U1") (pin "69") (pinfunction "VDD_69") (pintype "power_in"))
      (node (ref "U1") (pin "7") (pinfunction "VDD_7") (pintype "power_in"))
      (node (ref "U1") (pin "79") (pinfunction "VDD_79") (pintype "power_in"))
      (node (ref "U1") (pin "8") (pinfunction "VDDA_8") (pintype "power_in"))
      (node (ref "U1") (pin "90") (pinfunction "VDD_90") (pintype "power_in"))
      (node (ref "U10") (pin "2") (pinfunction "TCT_2") (pintype "passive"))
      (node (ref "U10") (pin "7") (pinfunction "RCT_7") (pintype "passive"))
    )
    (net (code "15") (name "Net-(C1-Pad1)") (class "Default")
      (node (ref "C1") (pin "1") (pinfunction "1_1") (pintype "passive"))
      (node (ref "R32") (pin "1") (pinfunction "1_1") (pintype "passive"))
      (node (ref "R43") (pin "1") (pinfunction "1_1") (pintype "passive"))
      (node (ref "R45") (pin "1") (pinfunction "1_1") (pintype "passive"))
      (node (ref "R46") (pin "1") (pinfunction "1_1") (pintype "passive"))
    )
    (net (code "16") (name "Net-(C1-Pad2)") (class "Default")
      (node (ref "C1") (pin "2") (pinfunction "2_2") (pintype "passive"))
      (node (ref "C31") (pin "1") (pinfunction "1_1") (pintype "passive"))
      (node (ref "R47") (pin "2") (pinfunction "2_2") (pintype "passive"))
      (node (ref "U14") (pin "10") (pinfunction "10_10") (pintype "passive"))
      (node (ref "U14") (pin "11") (pinfunction "11_11") (pintype "passive"))
      (node (ref "U14") (pin "12") (pinfunction "12_12") (pintype "passive"))
      (node (ref "U14") (pin "9") (pinfunction "9_9") (pintype "passive"))
    )
    (net (code "17") (name "Net-(C45-Pad1)") (class "Default")
      (node (ref "C45") (pin "1") (pinfunction "1_1") (pintype "passive"))
      (node (ref "R49") (pin "2") (pinfunction "2_2") (pintype "passive"))
      (node (ref "Y1") (pin "1") (pinfunction "1_1") (pintype "passive"))
    )
    (net (code "18") (name "Net-(D3-K)") (class "Default")
      (node (ref "D3") (pin "2") (pinfunction "K_2") (pintype "passive"))
      (node (ref "R31") (pin "2") (pinfunction "2_2") (pintype "passive"))
    )
    (net (code "19") (name "Net-(D4-K)") (class "Default")
      (node (ref "D4") (pin "2") (pinfunction "K_2") (pintype "passive"))
      (node (ref "R30") (pin "2") (pinfunction "2_2") (pintype "passive"))
    )
    (net (code "20") (name "Net-(R32-Pad2)") (class "Default")
      (node (ref "R32") (pin "2") (pinfunction "2_2") (pintype "passive"))
      (node (ref "U10") (pin "15") (pinfunction "CMT_15") (pintype "passive"))
    )
    (net (code "21") (name "Net-(R38-Pad2)") (class "Default")
      (node (ref "R38") (pin "2") (pinfunction "2_2") (pintype "passive"))
      (node (ref "R39") (pin "2") (pinfunction "2_2") (pintype "passive"))
      (node (ref "R42") (pin "2") (pinfunction "2_2") (pintype "passive"))
      (node (ref "TP11") (pin "1") (pintype "passive"))
    )
    (net (code "22") (name "Net-(R43-Pad2)") (class "Default")
      (node (ref "R43") (pin "2") (pinfunction "2_2") (pintype "passive"))
      (node (ref "U10") (pin "10") (pinfunction "CMT_10") (pintype "passive"))
    )
    (net (code "23") (name "Net-(R45-Pad2)") (class "Default")
      (node (ref "R45") (pin "2") (pinfunction "2_2") (pintype "passive"))
      (node (ref "U14") (pin "4") (pinfunction "4_4") (pintype "passive"))
      (node (ref "U14") (pin "5") (pinfunction "5_5") (pintype "passive"))
    )
    (net (code "24") (name "Net-(R46-Pad2)") (class "Default")
      (node (ref "R46") (pin "2") (pinfunction "2_2") (pintype "passive"))
      (node (ref "U14") (pin "7") (pinfunction "7_7") (pintype "passive"))
      (node (ref "U14") (pin "8") (pinfunction "8_8") (pintype "passive"))
    )
    (net (code "25") (name "Net-(R51-Pad1)") (class "Default")
      (node (ref "R51") (pin "1") (pinfunction "1_1") (pintype "passive"))
      (node (ref "RESET_SW1") (pin "3") (pinfunction "3_3") (pintype "passive"))
    )
    (net (code "26") (name "Net-(U1C-HIB)") (class "Default")
      (node (ref "TP9") (pin "1") (pintype "passive"))
      (node (ref "U1") (pin "65") (pinfunction "HIB_65") (pintype "output"))
    )
    (net (code "27") (name "Net-(U1C-OSC0)") (class "Default")
      (node (ref "C44") (pin "1") (pinfunction "1_1") (pintype "passive"))
      (node (ref "U1") (pin "88") (pinfunction "OSC0_88") (pintype "input"))
      (node (ref "Y1") (pin "3") (pinfunction "3_3") (pintype "passive"))
    )
    (net (code "28") (name "Net-(U1C-OSC1)") (class "Default")
      (node (ref "R49") (pin "1") (pinfunction "1_1") (pintype "passive"))
      (node (ref "U1") (pin "89") (pinfunction "OSC1_89") (pintype "output"))
    )
    (net (code "29") (name "Net-(U1C-RBIAS)") (class "Default")
      (node (ref "R25") (pin "1") (pinfunction "1_1") (pintype "passive"))
      (node (ref "U1") (pin "59") (pinfunction "RBIAS_59") (pintype "output"))
    )
    (net (code "30") (name "Net-(U1C-XOSC0)") (class "Default")
      (node (ref "C48") (pin "1") (pinfunction "1_1") (pintype "passive"))
      (node (ref "U1") (pin "66") (pinfunction "XOSC0_66") (pintype "input"))
      (node (ref "Y3") (pin "1") (pinfunction "1_1") (pintype "passive"))
    )
    (net (code "31") (name "Net-(U1C-XOSC1)") (class "Default")
      (node (ref "C47") (pin "1") (pinfunction "1_1") (pintype "passive"))
      (node (ref "U1") (pin "67") (pinfunction "XOSC1_67") (pintype "output"))
      (node (ref "Y3") (pin "2") (pinfunction "2_2") (pintype "passive"))
    )
    (net (code "32") (name "Net-(U1D-VBAT)") (class "Default")
      (node (ref "C3") (pin "2") (pinfunction "2_2") (pintype "passive"))
      (node (ref "R38") (pin "1") (pinfunction "1_1") (pintype "passive"))
      (node (ref "U1") (pin "68") (pinfunction "VBAT_68") (pintype "power_in"))
    )
    (net (code "33") (name "Net-(U4-EN1)") (class "Default")
      (node (ref "R26") (pin "2") (pinfunction "2_2") (pintype "passive"))
      (node (ref "R35") (pin "1") (pinfunction "1_1") (pintype "passive"))
      (node (ref "U4") (pin "3") (pinfunction "EN1_3") (pintype "input"))
    )
    (net (code "34") (name "Net-(U4-EN2)") (class "Default")
      (node (ref "JP7") (pin "1") (pinfunction "1_1") (pintype "passive"))
      (node (ref "R50") (pin "2") (pinfunction "2_2") (pintype "passive"))
      (node (ref "U4") (pin "4") (pinfunction "EN2_4") (pintype "input"))
    )
    (net (code "35") (name "Net-(U4-OC1)") (class "Default")
      (node (ref "R36") (pin "1") (pinfunction "1_1") (pintype "passive"))
      (node (ref "TP8") (pin "1") (pintype "passive"))
      (node (ref "U4") (pin "8") (pinfunction "OC1_8") (pintype "open_collector"))
    )
    (net (code "36") (name "Net-(U4-OC2)") (class "Default")
      (node (ref "JP6") (pin "1") (pinfunction "1_1") (pintype "passive"))
      (node (ref "U4") (pin "5") (pinfunction "OC2_5") (pintype "open_collector"))
    )
    (net (code "37") (name "PD6") (class "Default")
      (node (ref "JP7") (pin "2") (pinfunction "2_2") (pintype "passive"))
    )
    (net (code "38") (name "PF0") (class "Default")
      (node (ref "D4") (pin "1") (pinfunction "A_1") (pintype "passive"))
    )
    (net (code "39") (name "PF4") (class "Default")
      (node (ref "D3") (pin "1") (pinfunction "A_1") (pintype "passive"))
    )
    (net (code "40") (name "PQ4") (class "Default")
      (node (ref "JP6") (pin "2") (pinfunction "2_2") (pintype "passive"))
    )
    (net (code "41") (name "TARGET_VBUS") (class "Default")
      (node (ref "JP1") (pin "3") (pinfunction "3_3") (pintype "passive"))
      (node (ref "U4") (pin "6") (pinfunction "OUT2_6") (pintype "output"))
    )
    (net (code "42") (name "TGT_RST") (class "Default")
      (node (ref "C46") (pin "2") (pinfunction "2_2") (pintype "passive"))
      (node (ref "R44") (pin "1") (pinfunction "1_1") (pintype "passive"))
      (node (ref "R51") (pin "2") (pinfunction "2_2") (pintype "passive"))
      (node (ref "U1") (pin "70") (pinfunction "RST_70") (pintype "input"))
    )
    (net (code "43") (name "VBUS") (class "Default")
      (node (ref "JP1") (pin "2") (pinfunction "2_2") (pintype "passive"))
      (node (ref "JP1") (pin "4") (pinfunction "4_4") (pintype "passive"))
      (node (ref "JP1") (pin "6") (pinfunction "6_6") (pintype "passive"))
      (node (ref "R35") (pin "2") (pinfunction "2_2") (pintype "passive"))
      (node (ref "R36") (pin "2") (pinfunction "2_2") (pintype "passive"))
      (node (ref "U4") (pin "2") (pinfunction "IN_2") (pintype "power_in"))
    )
    (net (code "44") (name "VREF+") (class "Default")
      (node (ref "R41") (pin "2") (pinfunction "2_2") (pintype "passive"))
      (node (ref "TP13") (pin "1") (pintype "passive"))
      (node (ref "U1") (pin "9") (pinfunction "VREFA+_9") (pintype "power_in"))
    )
    (net (code "45") (name "Wake") (class "Default")
      (node (ref "R42") (pin "1") (pinfunction "1_1") (pintype "passive"))
      (node (ref "TP10") (pin "1") (pintype "passive"))
      (node (ref "U1") (pin "64") (pinfunction "WAKE_64") (pintype "input"))
      (node (ref "Wake_SW4") (pin "3") (pinfunction "3_3") (pintype "passive"))
    )
    (net (code "46") (name "unconnected-(JP1-Pad1)") (class "Default")
      (node (ref "JP1") (pin "1") (pinfunction "1_1") (pintype "passive"))
    )
    (net (code "47") (name "unconnected-(U10-NC-Pad4)") (class "Default")
      (node (ref "U10") (pin "4") (pinfunction "NC_4") (pintype "passive"))
    )
    (net (code "48") (name "unconnected-(U10-NC-Pad5)") (class "Default")
      (node (ref "U10") (pin "5") (pinfunction "NC_5") (pintype "passive"))
    )
    (net (code "49") (name "unconnected-(U10-NC-Pad12)") (class "Default")
      (node (ref "U10") (pin "12") (pinfunction "NC_12") (pintype "passive"))
    )
    (net (code "50") (name "unconnected-(U10-NC-Pad13)") (class "Default")
      (node (ref "U10") (pin "13") (pinfunction "NC_13") (pintype "passive"))
    )
    (net (code "51") (name "unconnected-(Y1-GND-Pad2)") (class "Default")
      (node (ref "Y1") (pin "2") (pinfunction "GND_2") (pintype "power_in"))
    )
    (net (code "52") (name "unconnected-(Y1-GND-Pad4)") (class "Default")
      (node (ref "Y1") (pin "4") (pinfunction "GND_4") (pintype "power_in"))
    )
    (net (code "53") (name "unconnected-(Y3-GND-Pad3)") (class "Default")
      (node (ref "Y3") (pin "3") (pinfunction "GND_3") (pintype "power_in"))
    )
  )
)
